# intanRHS2116.net
KiCad netlist of a schematic drawn in Altium Designer
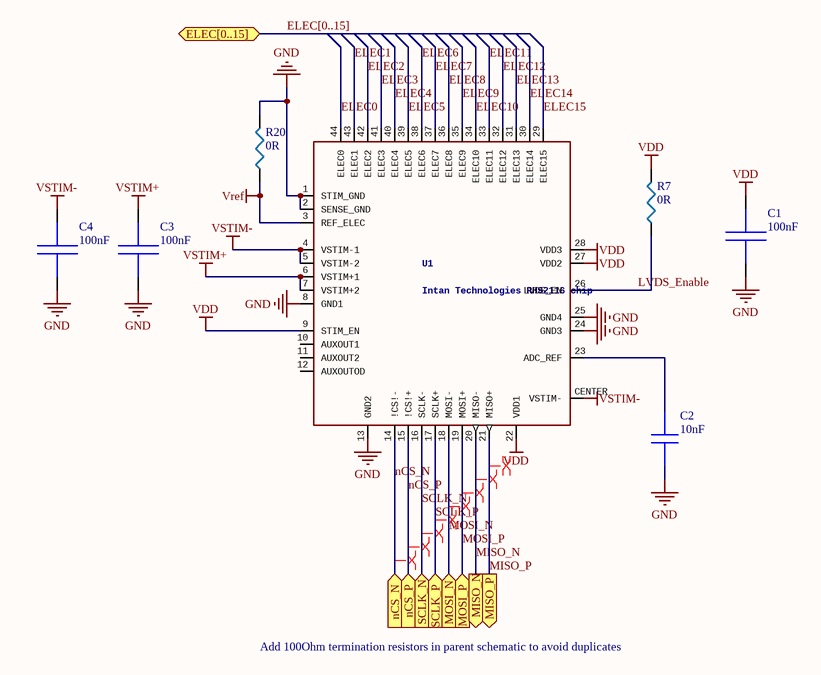
[diagram p0: intanRHS2116.SchDoc]

(export (version "E")
  (design (tool "Eeschema 10.0.6"))
  (components
    (comp (ref "C1")
      (value "100nF")
      (footprint "rcl_smd_chip_ipc:rcl_0402i_1005m_most")
      (description "Capacitor Non-polarized American Symbol")
      (fields
        (field (name "MANUFACTURER") "Yageo")
        (field (name "MANURACTURER PART NUMBER") "CC0402KRX7R8BB104")
      )
      (libsource (lib "rcl_passives") (part "capacitor_npol_ame"))
    )
    (comp (ref "C2")
      (value "10nF")
      (footprint "rcl_0402i_1005m_most")
      (description "Capacitor Non-polarized American Symbol")
      (fields
        (field (name "MANUFACTURER") "Murata Electronics North America")
        (field (name "MANUFACTURER PART NUMBER") "GRM155R71H103KA88D")
      )
      (libsource (lib "standard_components") (part "capacitor_npol_ame_10n"))
    )
    (comp (ref "C3")
      (value "100nF")
      (footprint "rcl_smd_chip_ipc:rcl_0402i_1005m_most")
      (description "Capacitor Non-polarized American Symbol")
      (fields
        (field (name "MANUFACTURER") "Yageo")
        (field (name "MANUFACTURER PART NUMBER") "CC0402KRX7R8BB104")
      )
      (libsource (lib "rcl_passives") (part "capacitor_npol_ame"))
    )
    (comp (ref "C4")
      (value "100nF")
      (footprint "rcl_smd_chip_ipc:rcl_0402i_1005m_most")
      (description "Capacitor Non-polarized American Symbol")
      (fields
        (field (name "MANUFACTURER") "Yageo")
        (field (name "MANURACTURER PART NUMBER") "CC0402KRX7R8BB104")
      )
      (libsource (lib "rcl_passives") (part "capacitor_npol_ame"))
    )
    (comp (ref "R7")
      (value "0R")
      (footprint "rcl_smd_chip_ipc:rcl_0402i_1005m_most")
      (description "RES SMD 0 OHM JUMPER 1/16W 0402")
      (fields
        (field (name "MANUFACTURER") "Vishay Dale")
        (field (name "MANUFACTURER PART NUMBER") "CRCW04020000Z0ED")
      )
      (libsource (lib "standard_components") (part "RES100"))
    )
    (comp (ref "R20")
      (value "0R")
      (footprint "rcl_smd_chip_ipc:rcl_0402i_1005m_most")
      (description "RES SMD 0 OHM JUMPER 1/16W 0402")
      (fields
        (field (name "MANUFACTURER") "Vishay Dale")
        (field (name "MANUFACTURER PART NUMBER") "CRCW04020000Z0ED")
      )
      (libsource (lib "standard_components") (part "RES100"))
    )
    (comp (ref "U1")
      (value "Intan Technologies RHS2116 chip")
      (footprint "QFN44_7_X_7")
      (fields
        (field (name "MANUFACTURER") "Intan Technologies")
        (field (name "MANUFACTURER PART NUMBER") "RHS2116")
      )
      (libsource (lib "intan_rhs2116") (part "RHS2116_QFN"))
    )
  )
  (nets
    (net (code "1") (name "/ELEC0") (class "Default")
      (node (ref "U1") (pin "44") (pinfunction "ELEC0_44") (pintype "passive"))
    )
    (net (code "2") (name "/ELEC1") (class "Default")
      (node (ref "U1") (pin "43") (pinfunction "ELEC1_43") (pintype "passive"))
    )
    (net (code "3") (name "/ELEC2") (class "Default")
      (node (ref "U1") (pin "42") (pinfunction "ELEC2_42") (pintype "passive"))
    )
    (net (code "4") (name "/ELEC3") (class "Default")
      (node (ref "U1") (pin "41") (pinfunction "ELEC3_41") (pintype "passive"))
    )
    (net (code "5") (name "/ELEC4") (class "Default")
      (node (ref "U1") (pin "40") (pinfunction "ELEC4_40") (pintype "passive"))
    )
    (net (code "6") (name "/ELEC5") (class "Default")
      (node (ref "U1") (pin "39") (pinfunction "ELEC5_39") (pintype "passive"))
    )
    (net (code "7") (name "/ELEC6") (class "Default")
      (node (ref "U1") (pin "38") (pinfunction "ELEC6_38") (pintype "passive"))
    )
    (net (code "8") (name "/ELEC7") (class "Default")
      (node (ref "U1") (pin "37") (pinfunction "ELEC7_37") (pintype "passive"))
    )
    (net (code "9") (name "/ELEC8") (class "Default")
      (node (ref "U1") (pin "36") (pinfunction "ELEC8_36") (pintype "passive"))
    )
    (net (code "10") (name "/ELEC9") (class "Default")
      (node (ref "U1") (pin "35") (pinfunction "ELEC9_35") (pintype "passive"))
    )
    (net (code "11") (name "/ELEC10") (class "Default")
      (node (ref "U1") (pin "34") (pinfunction "ELEC10_34") (pintype "passive"))
    )
    (net (code "12") (name "/ELEC11") (class "Default")
      (node (ref "U1") (pin "33") (pinfunction "ELEC11_33") (pintype "passive"))
    )
    (net (code "13") (name "/ELEC12") (class "Default")
      (node (ref "U1") (pin "32") (pinfunction "ELEC12_32") (pintype "passive"))
    )
    (net (code "14") (name "/ELEC13") (class "Default")
      (node (ref "U1") (pin "31") (pinfunction "ELEC13_31") (pintype "passive"))
    )
    (net (code "15") (name "/ELEC14") (class "Default")
      (node (ref "U1") (pin "30") (pinfunction "ELEC14_30") (pintype "passive"))
    )
    (net (code "16") (name "/ELEC15") (class "Default")
      (node (ref "U1") (pin "29") (pinfunction "ELEC15_29") (pintype "passive"))
    )
    (net (code "18") (name "/LVDS_Enable") (class "Default")
      (node (ref "R7") (pin "1") (pinfunction "1_1") (pintype "passive"))
      (node (ref "U1") (pin "26") (pinfunction "LVDS_EN_26") (pintype "passive"))
    )
    (net (code "19") (name "/MISO_N") (class "Default")
      (node (ref "U1") (pin "20") (pinfunction "MISO-_20") (pintype "output"))
    )
    (net (code "20") (name "/MISO_P") (class "Default")
      (node (ref "U1") (pin "21") (pinfunction "MISO+_21") (pintype "output"))
    )
    (net (code "21") (name "/MOSI_N") (class "Default")
      (node (ref "U1") (pin "18") (pinfunction "MOSI-_18") (pintype "passive"))
    )
    (net (code "22") (name "/MOSI_P") (class "Default")
      (node (ref "U1") (pin "19") (pinfunction "MOSI+_19") (pintype "passive"))
    )
    (net (code "23") (name "/SCLK_N") (class "Default")
      (node (ref "U1") (pin "16") (pinfunction "SCLK-_16") (pintype "passive"))
    )
    (net (code "24") (name "/SCLK_P") (class "Default")
      (node (ref "U1") (pin "17") (pinfunction "SCLK+_17") (pintype "passive"))
    )
    (net (code "25") (name "/nCS_N") (class "Default")
      (node (ref "U1") (pin "14") (pinfunction "!CS!-_14") (pintype "passive"))
    )
    (net (code "26") (name "/nCS_P") (class "Default")
      (node (ref "U1") (pin "15") (pinfunction "!CS!+_15") (pintype "passive"))
    )
    (net (code "27") (name "GND") (class "Default")
      (node (ref "C1") (pin "1") (pinfunction "1_1") (pintype "passive"))
      (node (ref "C2") (pin "1") (pinfunction "1_1") (pintype "passive"))
      (node (ref "C3") (pin "1") (pinfunction "1_1") (pintype "passive"))
      (node (ref "C4") (pin "1") (pinfunction "1_1") (pintype "passive"))
      (node (ref "R20") (pin "2") (pinfunction "2_2") (pintype "passive"))
      (node (ref "U1") (pin "1") (pinfunction "STIM_GND_1") (pintype "power_in"))
      (node (ref "U1") (pin "13") (pinfunction "GND2_13") (pintype "power_in"))
      (node (ref "U1") (pin "2") (pinfunction "SENSE_GND_2") (pintype "power_in"))
      (node (ref "U1") (pin "24") (pinfunction "GND3_24") (pintype "power_in"))
      (node (ref "U1") (pin "25") (pinfunction "GND4_25") (pintype "power_in"))
      (node (ref "U1") (pin "8") (pinfunction "GND1_8") (pintype "power_in"))
    )
    (net (code "28") (name "Net-(U1-ADC_REF)") (class "Default")
      (node (ref "C2") (pin "2") (pinfunction "2_2") (pintype "passive"))
      (node (ref "U1") (pin "23") (pinfunction "ADC_REF_23") (pintype "passive"))
    )
    (net (code "29") (name "VDD") (class "Default")
      (node (ref "C1") (pin "2") (pinfunction "2_2") (pintype "passive"))
      (node (ref "R7") (pin "2") (pinfunction "2_2") (pintype "passive"))
      (node (ref "U1") (pin "22") (pinfunction "VDD1_22") (pintype "power_in"))
      (node (ref "U1") (pin "27") (pinfunction "VDD2_27") (pintype "power_in"))
      (node (ref "U1") (pin "28") (pinfunction "VDD3_28") (pintype "power_in"))
      (node (ref "U1") (pin "9") (pinfunction "STIM_EN_9") (pintype "passive"))
    )
    (net (code "30") (name "VSTIM+") (class "Default")
      (node (ref "C3") (pin "2") (pinfunction "2_2") (pintype "passive"))
      (node (ref "U1") (pin "6") (pinfunction "VSTIM+1_6") (pintype "power_in"))
      (node (ref "U1") (pin "7") (pinfunction "VSTIM+2_7") (pintype "power_in"))
    )
    (net (code "31") (name "VSTIM-") (class "Default")
      (node (ref "C4") (pin "2") (pinfunction "2_2") (pintype "passive"))
      (node (ref "U1") (pin "4") (pinfunction "VSTIM-1_4") (pintype "power_in"))
      (node (ref "U1") (pin "5") (pinfunction "VSTIM-2_5") (pintype "power_in"))
      (node (ref "U1") (pin "CENTER") (pinfunction "VSTIM-_CENTER") (pintype "power_in"))
    )
    (net (code "32") (name "Vref") (class "Default")
      (node (ref "R20") (pin "1") (pinfunction "1_1") (pintype "passive"))
      (node (ref "U1") (pin "3") (pinfunction "REF_ELEC_3") (pintype "passive"))
    )
    (net (code "33") (name "unconnected-(U1-AUXOUT1-Pad10)") (class "Default")
      (node (ref "U1") (pin "10") (pinfunction "AUXOUT1_10") (pintype "tri_state"))
    )
    (net (code "34") (name "unconnected-(U1-AUXOUT2-Pad11)") (class "Default")
      (node (ref "U1") (pin "11") (pinfunction "AUXOUT2_11") (pintype "tri_state"))
    )
    (net (code "35") (name "unconnected-(U1-AUXOUTOD-Pad12)") (class "Default")
      (node (ref "U1") (pin "12") (pinfunction "AUXOUTOD_12") (pintype "open_collector"))
    )
  )
)
